# D1-Garage-Relay.net
KiCad netlist of a schematic drawn in EAGLE
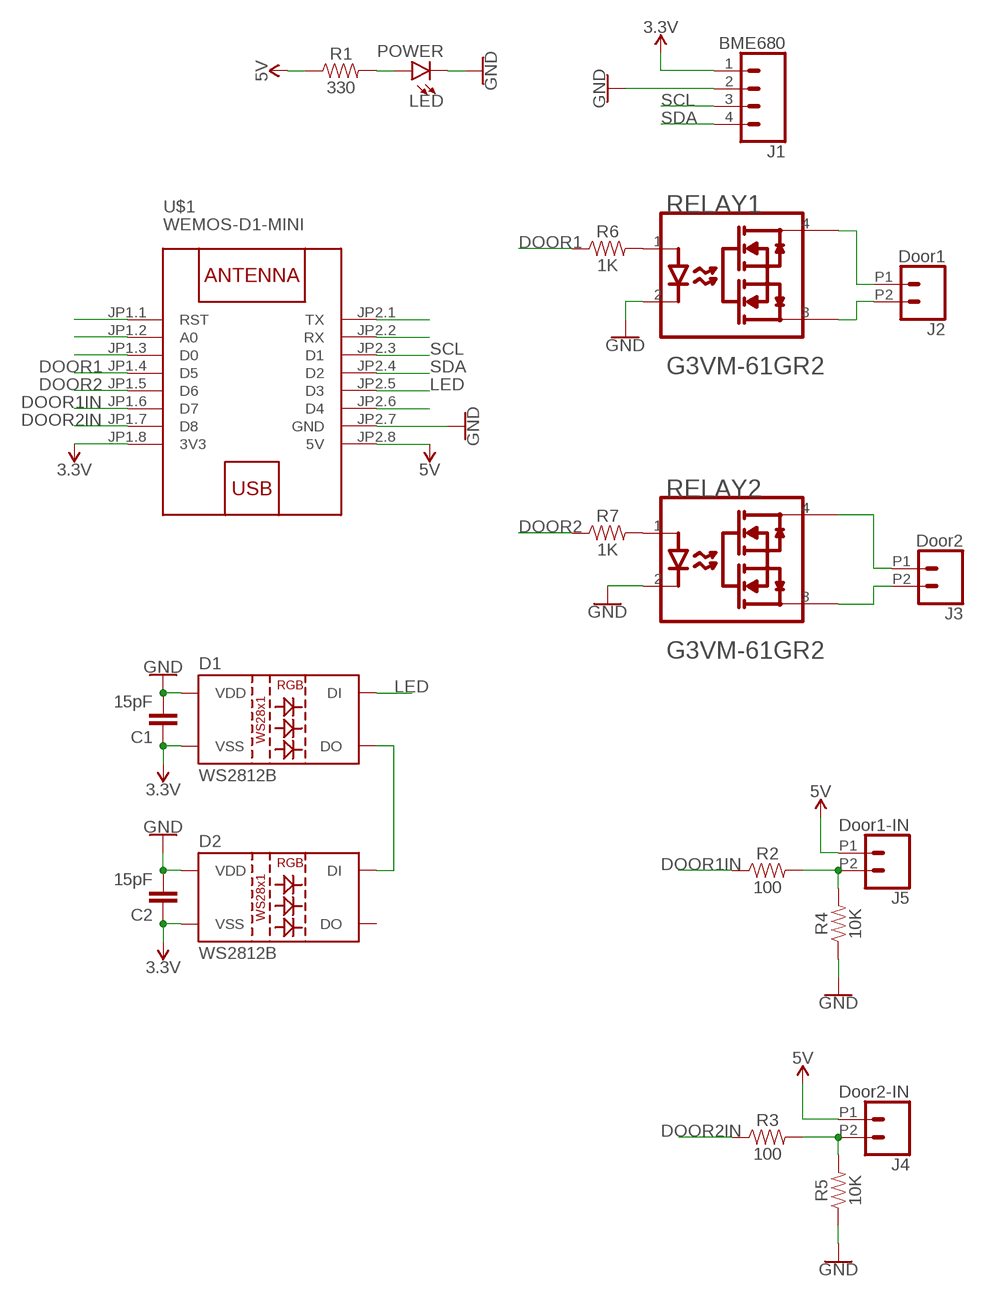
[diagram p0: schematic, sheet 1]

(export (version "E")
  (design (tool "Eeschema 10.0.6"))
  (components
    (comp (ref "C1")
      (value "15pF")
      (footprint "eagle-import:0603")
      (libsource (lib "eagle-import") (part "15PF-0603-50V-5%"))
    )
    (comp (ref "C2")
      (value "15pF")
      (footprint "eagle-import:0603")
      (libsource (lib "eagle-import") (part "15PF-0603-50V-5%"))
    )
    (comp (ref "D1")
      (value "WS2812B")
      (footprint "eagle-import:WS2812B")
      (libsource (lib "eagle-import") (part "WS2812B"))
    )
    (comp (ref "D2")
      (value "WS2812B")
      (footprint "eagle-import:WS2812B")
      (libsource (lib "eagle-import") (part "WS2812B"))
    )
    (comp (ref "J1")
      (value "BME680")
      (footprint "eagle-import:1X04")
      (libsource (lib "eagle-import") (part "CONN_04"))
    )
    (comp (ref "J2")
      (value "Door1")
      (footprint "eagle-import:1X02_2.54_SCREWTERM")
      (libsource (lib "eagle-import") (part "CONN_022.54MM_SCREWTERM"))
    )
    (comp (ref "J3")
      (value "Door2")
      (footprint "eagle-import:1X02_2.54_SCREWTERM")
      (libsource (lib "eagle-import") (part "CONN_022.54MM_SCREWTERM"))
    )
    (comp (ref "J4")
      (value "Door2-IN")
      (footprint "eagle-import:1X02_2.54_SCREWTERM")
      (libsource (lib "eagle-import") (part "CONN_022.54MM_SCREWTERM"))
    )
    (comp (ref "J5")
      (value "Door1-IN")
      (footprint "eagle-import:1X02_2.54_SCREWTERM")
      (libsource (lib "eagle-import") (part "CONN_022.54MM_SCREWTERM"))
    )
    (comp (ref "LED")
      (value "POWER")
      (footprint "eagle-import:LED-1206")
      (libsource (lib "eagle-import") (part "LED1206"))
    )
    (comp (ref "R1")
      (value "330")
      (footprint "eagle-import:0603")
      (libsource (lib "eagle-import") (part "RESISTOR0603"))
    )
    (comp (ref "R2")
      (value "100")
      (footprint "eagle-import:0603")
      (libsource (lib "eagle-import") (part "RESISTOR0603"))
    )
    (comp (ref "R3")
      (value "100")
      (footprint "eagle-import:0603")
      (libsource (lib "eagle-import") (part "RESISTOR0603"))
    )
    (comp (ref "R4")
      (value "10K")
      (footprint "eagle-import:0603")
      (libsource (lib "eagle-import") (part "RESISTOR0603"))
    )
    (comp (ref "R5")
      (value "10K")
      (footprint "eagle-import:0603")
      (libsource (lib "eagle-import") (part "RESISTOR0603"))
    )
    (comp (ref "R6")
      (value "1K")
      (footprint "eagle-import:0603")
      (libsource (lib "eagle-import") (part "RESISTOR0603"))
    )
    (comp (ref "R7")
      (value "1K")
      (footprint "eagle-import:0603")
      (libsource (lib "eagle-import") (part "RESISTOR0603"))
    )
    (comp (ref "RELAY1")
      (value "AQY282SZ")
      (footprint "eagle-import:OMRON_G3VM-61GR2_3")
      (fields
        (field (name "DIGIKEY_PART_NUMBER") "Z8611-ND")
        (field (name "MF") "Omron")
        (field (name "MOUSER_PART_NUMBER") "653-G3VM61GR2")
      )
      (libsource (lib "eagle-import") (part "OMRON_G3VM-61GR2OMRON_G3VM-61GR2_0_3"))
    )
    (comp (ref "RELAY2")
      (value "AQY282SZ")
      (footprint "eagle-import:OMRON_G3VM-61GR2_3")
      (fields
        (field (name "DIGIKEY_PART_NUMBER") "Z8611-ND")
        (field (name "MF") "Omron")
        (field (name "MOUSER_PART_NUMBER") "653-G3VM61GR2")
      )
      (libsource (lib "eagle-import") (part "OMRON_G3VM-61GR2OMRON_G3VM-61GR2_0_3"))
    )
    (comp (ref "U$1")
      (value "WEMOS-D1-MINI")
      (footprint "eagle-import:WEMOS-D1-MINI")
      (libsource (lib "eagle-import") (part "WEMOS-D1-MINI"))
    )
  )
  (nets
    (net (code "1") (name "/DOOR1") (class "Default")
      (node (ref "R6") (pin "1") (pinfunction "1_1") (pintype "passive"))
      (node (ref "U$1") (pin "JP1.4") (pinfunction "D5_JP1.4") (pintype "bidirectional"))
    )
    (net (code "2") (name "/DOOR1IN") (class "Default")
      (node (ref "R2") (pin "1") (pinfunction "1_1") (pintype "passive"))
      (node (ref "U$1") (pin "JP1.6") (pinfunction "D7_JP1.6") (pintype "bidirectional"))
    )
    (net (code "3") (name "/DOOR2") (class "Default")
      (node (ref "R7") (pin "1") (pinfunction "1_1") (pintype "passive"))
      (node (ref "U$1") (pin "JP1.5") (pinfunction "D6_JP1.5") (pintype "bidirectional"))
    )
    (net (code "4") (name "/DOOR2IN") (class "Default")
      (node (ref "R3") (pin "1") (pinfunction "1_1") (pintype "passive"))
      (node (ref "U$1") (pin "JP1.7") (pinfunction "D8_JP1.7") (pintype "bidirectional"))
    )
    (net (code "5") (name "/LED") (class "Default")
      (node (ref "D1") (pin "4") (pinfunction "DI_4") (pintype "bidirectional"))
      (node (ref "U$1") (pin "JP2.5") (pinfunction "D3_JP2.5") (pintype "bidirectional"))
    )
    (net (code "6") (name "/SCL") (class "Default")
      (node (ref "J1") (pin "3") (pinfunction "3_3") (pintype "passive"))
      (node (ref "U$1") (pin "JP2.3") (pinfunction "D1_JP2.3") (pintype "bidirectional"))
    )
    (net (code "7") (name "/SDA") (class "Default")
      (node (ref "J1") (pin "4") (pinfunction "4_4") (pintype "passive"))
      (node (ref "U$1") (pin "JP2.4") (pinfunction "D2_JP2.4") (pintype "bidirectional"))
    )
    (net (code "8") (name "3.3V") (class "Default")
      (node (ref "C1") (pin "1") (pinfunction "1_1") (pintype "passive"))
      (node (ref "C2") (pin "1") (pinfunction "1_1") (pintype "passive"))
      (node (ref "D1") (pin "3") (pinfunction "VSS_3") (pintype "bidirectional"))
      (node (ref "D2") (pin "3") (pinfunction "VSS_3") (pintype "bidirectional"))
      (node (ref "J1") (pin "1") (pinfunction "1_1") (pintype "passive"))
      (node (ref "U$1") (pin "JP1.8") (pinfunction "3V3_JP1.8") (pintype "power_in"))
    )
    (net (code "9") (name "5V") (class "Default")
      (node (ref "J4") (pin "P1") (pinfunction "1_P1") (pintype "passive"))
      (node (ref "J5") (pin "P1") (pinfunction "1_P1") (pintype "passive"))
      (node (ref "R1") (pin "1") (pinfunction "1_1") (pintype "passive"))
      (node (ref "U$1") (pin "JP2.8") (pinfunction "5V_JP2.8") (pintype "power_in"))
    )
    (net (code "10") (name "GND") (class "Default")
      (node (ref "C1") (pin "2") (pinfunction "2_2") (pintype "passive"))
      (node (ref "C2") (pin "2") (pinfunction "2_2") (pintype "passive"))
      (node (ref "D1") (pin "1") (pinfunction "VDD_1") (pintype "bidirectional"))
      (node (ref "D2") (pin "1") (pinfunction "VDD_1") (pintype "bidirectional"))
      (node (ref "J1") (pin "2") (pinfunction "2_2") (pintype "passive"))
      (node (ref "LED") (pin "C") (pinfunction "C_C") (pintype "passive"))
      (node (ref "R4") (pin "1") (pinfunction "1_1") (pintype "passive"))
      (node (ref "R5") (pin "1") (pinfunction "1_1") (pintype "passive"))
      (node (ref "RELAY1") (pin "2") (pinfunction "CATHODE_2") (pintype "passive"))
      (node (ref "RELAY2") (pin "2") (pinfunction "CATHODE_2") (pintype "passive"))
      (node (ref "U$1") (pin "JP2.7") (pinfunction "GND_JP2.7") (pintype "power_in"))
    )
    (net (code "11") (name "Net-(D1-DO)") (class "Default")
      (node (ref "D1") (pin "2") (pinfunction "DO_2") (pintype "bidirectional"))
      (node (ref "D2") (pin "4") (pinfunction "DI_4") (pintype "bidirectional"))
    )
    (net (code "12") (name "Net-(J2-1)") (class "Default")
      (node (ref "J2") (pin "P1") (pinfunction "1_P1") (pintype "passive"))
      (node (ref "RELAY1") (pin "4") (pinfunction "2_DRAIN_4") (pintype "passive"))
    )
    (net (code "13") (name "Net-(J2-2)") (class "Default")
      (node (ref "J2") (pin "P2") (pinfunction "2_P2") (pintype "passive"))
      (node (ref "RELAY1") (pin "3") (pinfunction "1_DRAIN_3") (pintype "passive"))
    )
    (net (code "14") (name "Net-(J3-1)") (class "Default")
      (node (ref "J3") (pin "P1") (pinfunction "1_P1") (pintype "passive"))
      (node (ref "RELAY2") (pin "4") (pinfunction "2_DRAIN_4") (pintype "passive"))
    )
    (net (code "15") (name "Net-(J3-2)") (class "Default")
      (node (ref "J3") (pin "P2") (pinfunction "2_P2") (pintype "passive"))
      (node (ref "RELAY2") (pin "3") (pinfunction "1_DRAIN_3") (pintype "passive"))
    )
    (net (code "16") (name "Net-(J4-2)") (class "Default")
      (node (ref "J4") (pin "P2") (pinfunction "2_P2") (pintype "passive"))
      (node (ref "R3") (pin "2") (pinfunction "2_2") (pintype "passive"))
      (node (ref "R5") (pin "2") (pinfunction "2_2") (pintype "passive"))
    )
    (net (code "17") (name "Net-(J5-2)") (class "Default")
      (node (ref "J5") (pin "P2") (pinfunction "2_P2") (pintype "passive"))
      (node (ref "R2") (pin "2") (pinfunction "2_2") (pintype "passive"))
      (node (ref "R4") (pin "2") (pinfunction "2_2") (pintype "passive"))
    )
    (net (code "18") (name "Net-(LED-PadA)") (class "Default")
      (node (ref "LED") (pin "A") (pinfunction "A_A") (pintype "passive"))
      (node (ref "R1") (pin "2") (pinfunction "2_2") (pintype "passive"))
    )
    (net (code "19") (name "Net-(RELAY1-ANODE)") (class "Default")
      (node (ref "R6") (pin "2") (pinfunction "2_2") (pintype "passive"))
      (node (ref "RELAY1") (pin "1") (pinfunction "ANODE_1") (pintype "passive"))
    )
    (net (code "20") (name "Net-(RELAY2-ANODE)") (class "Default")
      (node (ref "R7") (pin "2") (pinfunction "2_2") (pintype "passive"))
      (node (ref "RELAY2") (pin "1") (pinfunction "ANODE_1") (pintype "passive"))
    )
    (net (code "21") (name "unconnected-(D2-DO-Pad2)") (class "Default")
      (node (ref "D2") (pin "2") (pinfunction "DO_2") (pintype "bidirectional"))
    )
    (net (code "22") (name "unconnected-(U$1-A0-PadJP1.2)") (class "Default")
      (node (ref "U$1") (pin "JP1.2") (pinfunction "A0_JP1.2") (pintype "bidirectional"))
    )
    (net (code "23") (name "unconnected-(U$1-D0-PadJP1.3)") (class "Default")
      (node (ref "U$1") (pin "JP1.3") (pinfunction "D0_JP1.3") (pintype "bidirectional"))
    )
    (net (code "24") (name "unconnected-(U$1-D4-PadJP2.6)") (class "Default")
      (node (ref "U$1") (pin "JP2.6") (pinfunction "D4_JP2.6") (pintype "bidirectional"))
    )
    (net (code "25") (name "unconnected-(U$1-RST-PadJP1.1)") (class "Default")
      (node (ref "U$1") (pin "JP1.1") (pinfunction "RST_JP1.1") (pintype "bidirectional"))
    )
    (net (code "26") (name "unconnected-(U$1-RX-PadJP2.2)") (class "Default")
      (node (ref "U$1") (pin "JP2.2") (pinfunction "RX_JP2.2") (pintype "bidirectional"))
    )
    (net (code "27") (name "unconnected-(U$1-TX-PadJP2.1)") (class "Default")
      (node (ref "U$1") (pin "JP2.1") (pinfunction "TX_JP2.1") (pintype "bidirectional"))
    )
  )
)
